# WIFI.net
KiCad netlist of a schematic drawn in Altium Designer
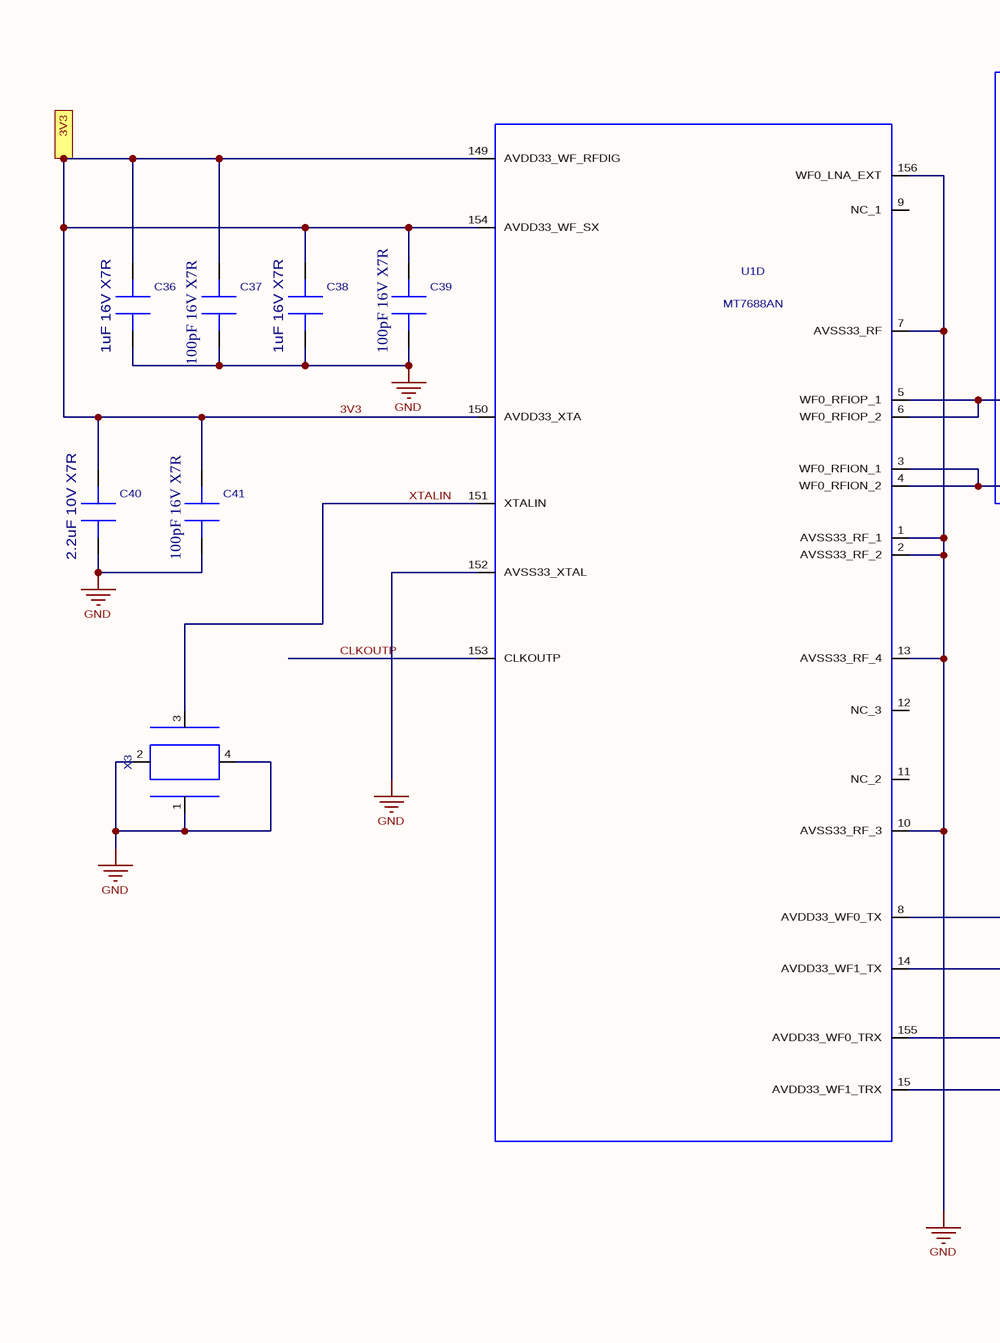
[diagram p0: WIFI.SchDoc, left]
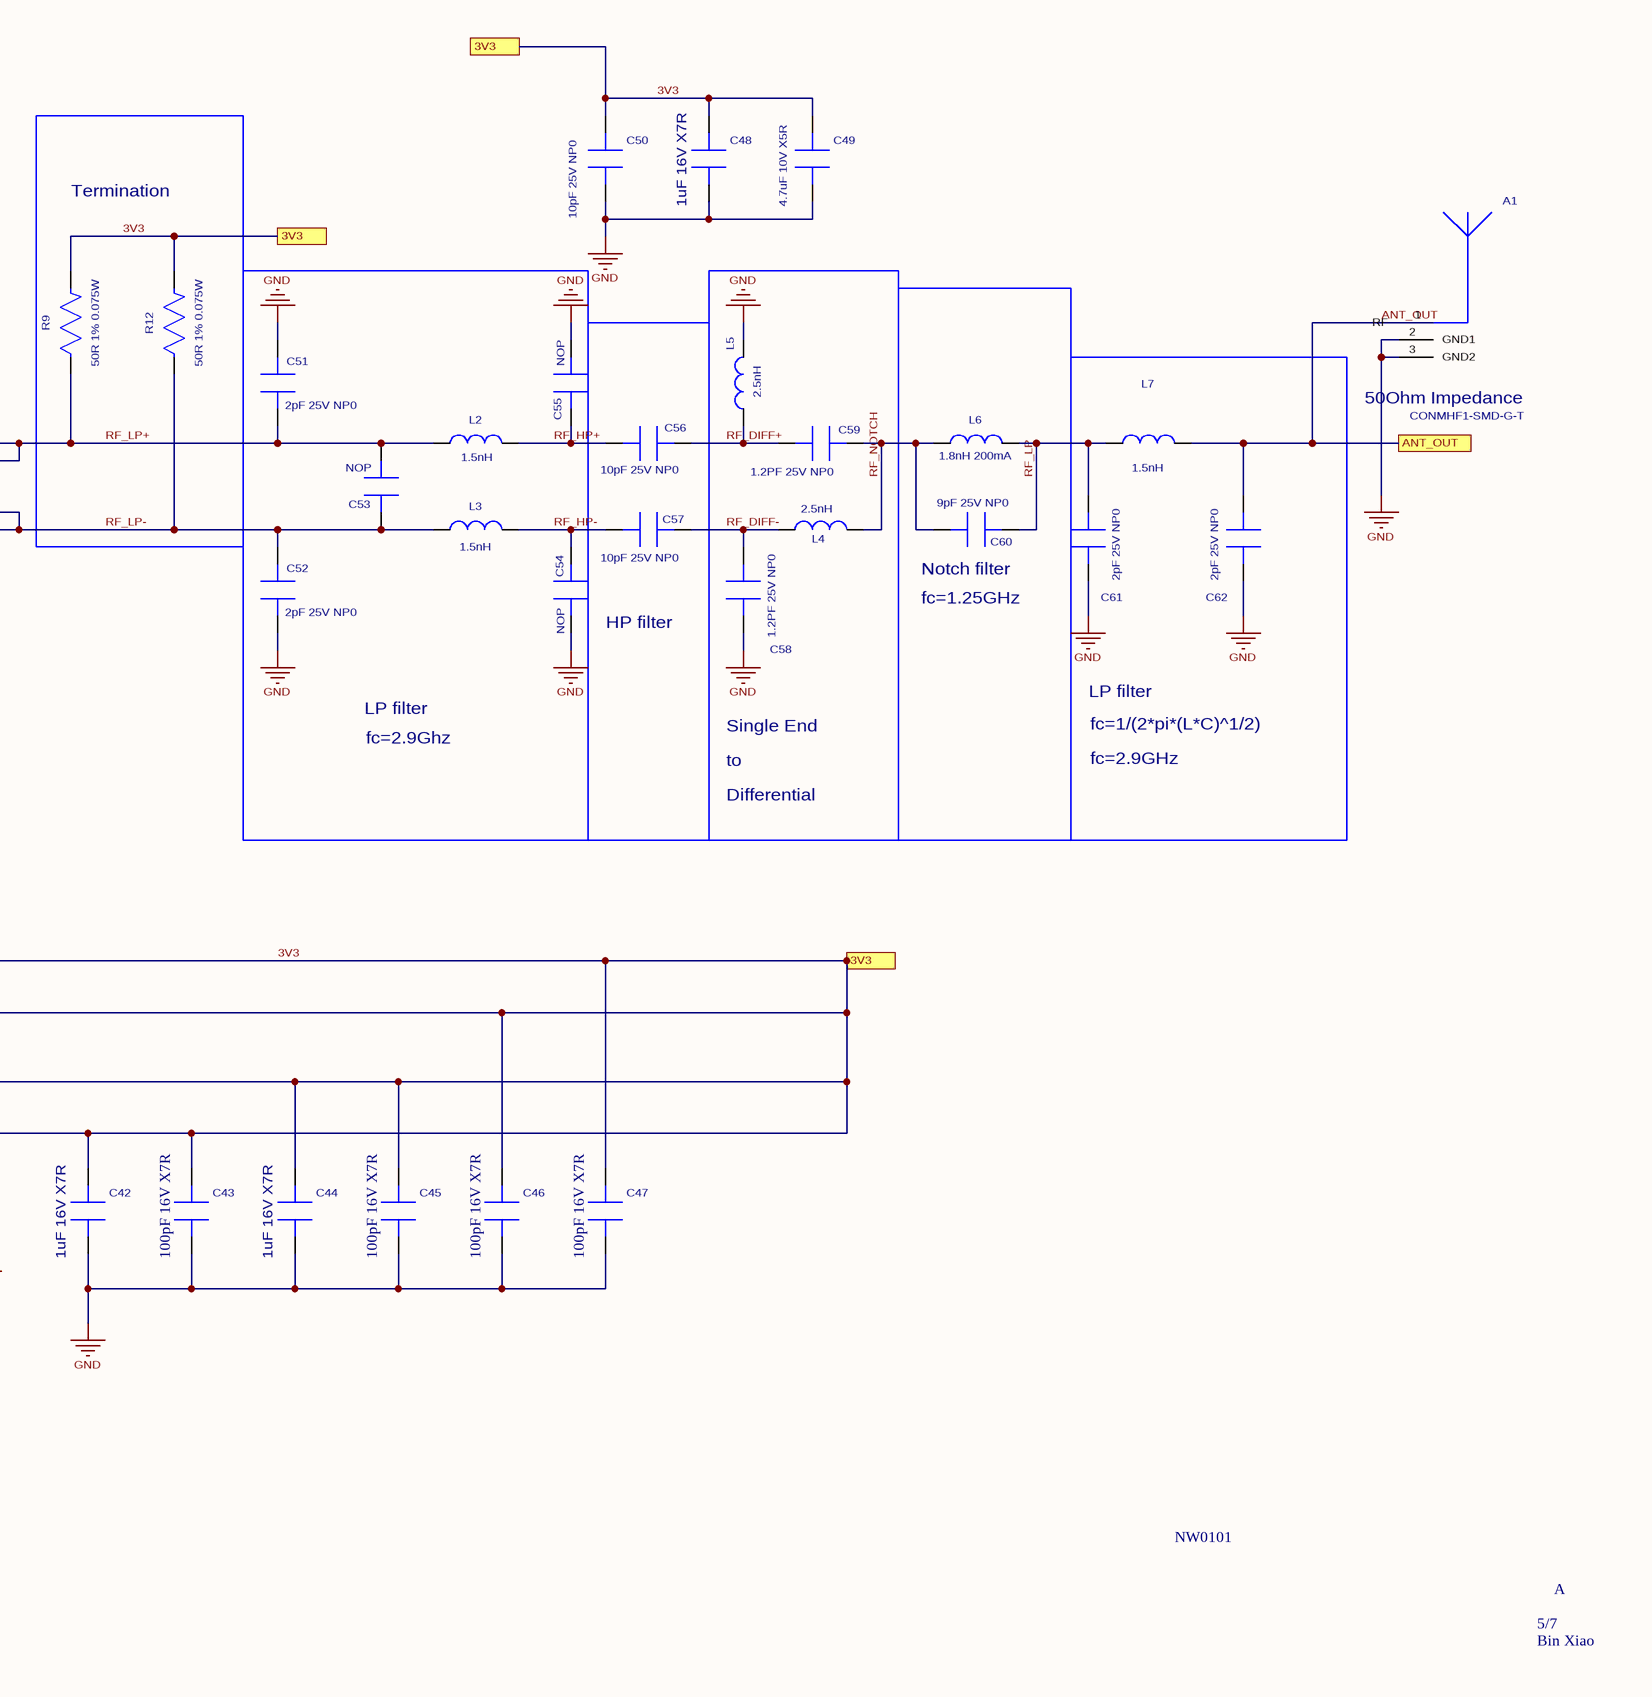
[diagram p1: WIFI.SchDoc, right]

(export (version "E")
  (design (tool "Eeschema 10.0.6"))
  (components
    (comp (ref "A1")
      (value "CONMHF1-SMD-G-T")
      (footprint "CONMHF1-SMD-G-T")
      (description "CONN UMC JACK STR SMD")
      (fields (field (name "MANUFACTURER") "Linx Technologies Inc."))
      (libsource (lib "*") (part "CONMHF1-SMD-G-T"))
    )
    (comp (ref "C36")
      (value "1uF 16V X7R")
      (footprint "C0402")
      (description "CAP CER 1UF 6.3V X7R 0402")
      (fields
        (field (name "PART NUMBER") "GRM155R70J105KA12D")
        (field (name "MANUFACTURER") "Murata Electronics")
      )
      (libsource (lib "NetworkModule") (part "CAP0402-105-6.3V-X7R"))
    )
    (comp (ref "C37")
      (value "100pF 16V X7R")
      (footprint "C0201")
      (description "CAP CER 100PF 16V X7R 0201")
      (fields
        (field (name "PART NUMBER") "0201B101K160CT")
        (field (name "MANUFACTURER") "Walsin Technology Corporation")
      )
      (libsource (lib "NetworkModule") (part "CAP0201-101-16V-X7R"))
    )
    (comp (ref "C38")
      (value "1uF 16V X7R")
      (footprint "C0402")
      (description "CAP CER 1UF 6.3V X7R 0402")
      (fields
        (field (name "PART NUMBER") "GRM155R70J105KA12D")
        (field (name "MANUFACTURER") "Murata Electronics")
      )
      (libsource (lib "NetworkModule") (part "CAP0402-105-6.3V-X7R"))
    )
    (comp (ref "C39")
      (value "100pF 16V X7R")
      (footprint "C0201")
      (description "CAP CER 100PF 16V X7R 0201")
      (fields
        (field (name "PART NUMBER") "0201B101K160CT")
        (field (name "MANUFACTURER") "Walsin Technology Corporation")
      )
      (libsource (lib "NetworkModule") (part "CAP0201-101-16V-X7R"))
    )
    (comp (ref "C40")
      (value "2.2uF 10V X7R")
      (footprint "C0402")
      (description "CAP CER 2.2UF 10V X7R 0402")
      (fields
        (field (name "PART NUMBER") "GRM155Z71A225KE01D")
        (field (name "MANUFACTURER") "Murata Electronics")
      )
      (libsource (lib "NetworkModule") (part "CAP0402-225-6.3V-X7R"))
    )
    (comp (ref "C41")
      (value "100pF 16V X7R")
      (footprint "C0201")
      (description "CAP CER 100PF 16V X7R 0201")
      (fields
        (field (name "PART NUMBER") "0201B101K160CT")
        (field (name "MANUFACTURER") "Walsin Technology Corporation")
      )
      (libsource (lib "NetworkModule") (part "CAP0201-101-16V-X7R"))
    )
    (comp (ref "C42")
      (value "1uF 16V X7R")
      (footprint "C0402")
      (description "CAP CER 1UF 6.3V X7R 0402")
      (fields
        (field (name "PART NUMBER") "GRM155R70J105KA12D")
        (field (name "MANUFACTURER") "Murata Electronics")
      )
      (libsource (lib "NetworkModule") (part "CAP0402-105-6.3V-X7R"))
    )
    (comp (ref "C43")
      (value "100pF 16V X7R")
      (footprint "C0201")
      (description "CAP CER 100PF 16V X7R 0201")
      (fields
        (field (name "PART NUMBER") "0201B101K160CT")
        (field (name "MANUFACTURER") "Walsin Technology Corporation")
      )
      (libsource (lib "NetworkModule") (part "CAP0201-101-16V-X7R"))
    )
    (comp (ref "C44")
      (value "1uF 16V X7R")
      (footprint "C0402")
      (description "CAP CER 1UF 6.3V X7R 0402")
      (fields
        (field (name "PART NUMBER") "GRM155R70J105KA12D")
        (field (name "MANUFACTURER") "Murata Electronics")
      )
      (libsource (lib "NetworkModule") (part "CAP0402-105-6.3V-X7R"))
    )
    (comp (ref "C45")
      (value "100pF 16V X7R")
      (footprint "C0201")
      (description "CAP CER 100PF 16V X7R 0201")
      (fields
        (field (name "PART NUMBER") "0201B101K160CT")
        (field (name "MANUFACTURER") "Walsin Technology Corporation")
      )
      (libsource (lib "NetworkModule") (part "CAP0201-101-16V-X7R"))
    )
    (comp (ref "C46")
      (value "100pF 16V X7R")
      (footprint "C0201")
      (description "CAP CER 100PF 16V X7R 0201")
      (fields
        (field (name "PART NUMBER") "0201B101K160CT")
        (field (name "MANUFACTURER") "Walsin Technology Corporation")
      )
      (libsource (lib "NetworkModule") (part "CAP0201-101-16V-X7R"))
    )
    (comp (ref "C47")
      (value "100pF 16V X7R")
      (footprint "C0201")
      (description "CAP CER 100PF 16V X7R 0201")
      (fields
        (field (name "PART NUMBER") "0201B101K160CT")
        (field (name "MANUFACTURER") "Walsin Technology Corporation")
      )
      (libsource (lib "NetworkModule") (part "CAP0201-101-16V-X7R"))
    )
    (comp (ref "C48")
      (value "1uF 16V X7R")
      (footprint "C0402")
      (description "CAP CER 1UF 6.3V X7R 0402")
      (fields
        (field (name "PART NUMBER") "GRM155R70J105KA12D")
        (field (name "MANUFACTURER") "Murata Electronics")
      )
      (libsource (lib "NetworkModule") (part "CAP0402-105-6.3V-X7R"))
    )
    (comp (ref "C49")
      (value "4.7uF 10V X5R")
      (footprint "C0402")
      (description "CAP CER 4.7UF 10V X5R 0402")
      (fields
        (field (name "PART NUMBER") "CL05A475MP5NRNC")
        (field (name "MANUFACTURER") "Samsung Electro-Mechanics")
      )
      (libsource (lib "NetworkModule") (part "CAP0402-475-10V-X5R"))
    )
    (comp (ref "C50")
      (value "10pF 25V NP0")
      (footprint "C0201")
      (description "CAP CER 10PF 25V C0G/NP0 0201")
      (fields
        (field (name "PART NUMBER") "0201N100J250CT")
        (field (name "MANUFACTURER") "Walsin Technology Corporation")
      )
      (libsource (lib "NetworkModule") (part "CAP0201-100-25V-NP0"))
    )
    (comp (ref "C51")
      (value "2pF 25V NP0")
      (footprint "C0201")
      (description "CAP CER 2PF 25V C0G/NP0 0201")
      (fields
        (field (name "PART NUMBER") "CL03C020BA3GNNC")
        (field (name "MANUFACTURER") "Samsung Electro-Mechanics")
      )
      (libsource (lib "NetworkModule") (part "CAP0201-020-25V-NP0"))
    )
    (comp (ref "C52")
      (value "2pF 25V NP0")
      (footprint "C0201")
      (description "CAP CER 2PF 25V C0G/NP0 0201")
      (fields
        (field (name "PART NUMBER") "CL03C020BA3GNNC")
        (field (name "MANUFACTURER") "Samsung Electro-Mechanics")
      )
      (libsource (lib "NetworkModule") (part "CAP0201-020-25V-NP0"))
    )
    (comp (ref "C53")
      (value "NOP")
      (footprint "C0201_NOP")
      (fields (field (name "Comment") "CAP0201-NOP"))
      (libsource (lib "NetworkModule") (part "CAP0201-NOP"))
    )
    (comp (ref "C54")
      (value "NOP")
      (footprint "C0201_NOP")
      (fields (field (name "Comment") "CAP0201-NOP"))
      (libsource (lib "NetworkModule") (part "CAP0201-NOP"))
    )
    (comp (ref "C55")
      (value "NOP")
      (footprint "C0201_NOP")
      (fields (field (name "Comment") "CAP0201-NOP"))
      (libsource (lib "NetworkModule") (part "CAP0201-NOP"))
    )
    (comp (ref "C56")
      (value "10pF 25V NP0")
      (footprint "C0201")
      (description "CAP CER 10PF 25V C0G/NP0 0201")
      (fields
        (field (name "PART NUMBER") "0201N100J250CT")
        (field (name "MANUFACTURER") "Walsin Technology Corporation")
      )
      (libsource (lib "NetworkModule") (part "CAP0201-100-25V-NP0"))
    )
    (comp (ref "C57")
      (value "10pF 25V NP0")
      (footprint "C0201")
      (description "CAP CER 10PF 25V C0G/NP0 0201")
      (fields
        (field (name "PART NUMBER") "0201N100J250CT")
        (field (name "MANUFACTURER") "Walsin Technology Corporation")
      )
      (libsource (lib "NetworkModule") (part "CAP0201-100-25V-NP0"))
    )
    (comp (ref "C58")
      (value "1.2PF 25V NP0")
      (footprint "C0201")
      (description "CAP CER 1.2PF 25V C0G/NP0 0201")
      (fields
        (field (name "PART NUMBER") "GRM0335C1E1R2WA01D")
        (field (name "MANUFACTURER") "Murata Electronics")
      )
      (libsource (lib "NetworkModule") (part "CAP0201-1R2-25V-NP0"))
    )
    (comp (ref "C59")
      (value "1.2PF 25V NP0")
      (footprint "C0201")
      (description "CAP CER 1.2PF 25V C0G/NP0 0201")
      (fields
        (field (name "PART NUMBER") "GRM0335C1E1R2WA01D")
        (field (name "MANUFACTURER") "Murata Electronics")
      )
      (libsource (lib "NetworkModule") (part "CAP0201-1R2-25V-NP0"))
    )
    (comp (ref "C60")
      (value "9pF 25V NP0")
      (footprint "C0201")
      (description "CAP CER 9PF 25V C0G 0201")
      (fields
        (field (name "PART NUMBER") "CGA1A2C0G1E090D030BA")
        (field (name "MANUFACTURER") "TDK Corporation")
      )
      (libsource (lib "NetworkModule") (part "CAP0201-090-100V-NP0"))
    )
    (comp (ref "C61")
      (value "2pF 25V NP0")
      (footprint "C0201")
      (description "CAP CER 2PF 25V C0G/NP0 0201")
      (fields
        (field (name "PART NUMBER") "CL03C020BA3GNNC")
        (field (name "MANUFACTURER") "Samsung Electro-Mechanics")
      )
      (libsource (lib "NetworkModule") (part "CAP0201-020-25V-NP0"))
    )
    (comp (ref "C62")
      (value "2pF 25V NP0")
      (footprint "C0201")
      (description "CAP CER 2PF 25V C0G/NP0 0201")
      (fields
        (field (name "PART NUMBER") "CL03C020BA3GNNC")
        (field (name "MANUFACTURER") "Samsung Electro-Mechanics")
      )
      (libsource (lib "NetworkModule") (part "CAP0201-020-25V-NP0"))
    )
    (comp (ref "L2")
      (value "1.5nH")
      (footprint "L0201")
      (description "INDUCTOR FIXED 1.5NH 0201")
      (fields
        (field (name "PART NUMBER") "WLCM0603TGB1N5TB")
        (field (name "MANUFACTURER") "Walsin Technology Corporation")
      )
      (libsource (lib "NetworkModule") (part "IND0201_1.5N_600MA"))
    )
    (comp (ref "L3")
      (value "1.5nH")
      (footprint "L0201")
      (description "INDUCTOR FIXED 1.5NH 0201")
      (fields
        (field (name "PART NUMBER") "WLCM0603TGB1N5TB")
        (field (name "MANUFACTURER") "Walsin Technology Corporation")
      )
      (libsource (lib "NetworkModule") (part "IND0201_1.5N_600MA"))
    )
    (comp (ref "L4")
      (value "2.5nH")
      (footprint "L0201")
      (description "FIXED IND 2.5NH 500MA 200MOHM SM")
      (fields
        (field (name "PART NUMBER") "LQP03TN2N5B02D")
        (field (name "MANUFACTURER") "Murata Electronics")
      )
      (libsource (lib "NetworkModule") (part "IND0201_2.5N_500MA"))
    )
    (comp (ref "L5")
      (value "2.5nH")
      (footprint "L0201")
      (description "FIXED IND 2.5NH 500MA 200MOHM SM")
      (fields
        (field (name "PART NUMBER") "LQP03TN2N5B02D")
        (field (name "MANUFACTURER") "Murata Electronics")
      )
      (libsource (lib "NetworkModule") (part "IND0201_2.5N_500MA"))
    )
    (comp (ref "L6")
      (value "1.8nH 200mA")
      (footprint "L0201")
      (description "FIXED IND 1.8NH 200MA 550MOHM SM")
      (fields
        (field (name "PART NUMBER") "1-2176075-8")
        (field (name "MANUFACTURER") "TE Connectivity Passive Product")
      )
      (libsource (lib "NetworkModule") (part "IND0201_1.8N_200MA"))
    )
    (comp (ref "L7")
      (value "1.5nH")
      (footprint "L0201")
      (description "INDUCTOR FIXED 1.5NH 0201")
      (fields
        (field (name "PART NUMBER") "WLCM0603TGB1N5TB")
        (field (name "MANUFACTURER") "Walsin Technology Corporation")
      )
      (libsource (lib "NetworkModule") (part "IND0201_1.5N_600MA"))
    )
    (comp (ref "R9")
      (value "50R 1% 0.075W")
      (footprint "R0201")
      (description "RES 50 OHM 0.1% 0.075W 0201")
      (fields (field (name "MANUFACTURER") "Vishay Dale") (field (name "PART NUMBER") "TNPW020150R0BEED"))
      (libsource (lib "NetworkModule") (part "RES0201-50R0"))
    )
    (comp (ref "R12")
      (value "50R 1% 0.075W")
      (footprint "R0201")
      (description "RES 50 OHM 0.1% 0.075W 0201")
      (fields (field (name "MANUFACTURER") "Vishay Dale") (field (name "PART NUMBER") "TNPW020150R0BEED"))
      (libsource (lib "NetworkModule") (part "RES0201-50R0"))
    )
    (comp (ref "U1")
      (value "MT7688AN")
      (footprint "DR-QFN-128")
      (description "580Mhz 32bits Networking Processor")
      (fields (field (name "MANUFACTURER") "MediaTek Inc"))
      (libsource (lib "*") (part "MT7688AN"))
    )
    (comp (ref "X3")
      (value "R2520-40.000-12-F-1010-TR-NS1")
      (footprint "R2520-40.000-12-F-1010-TR-NS1")
      (description "CRYSTAL 40.0000MHZ 12PF SMD")
      (fields (field (name "MANUFACTURER") "Raltron Electronics"))
      (libsource (lib "*") (part "R2520-40.000-12-F-1010-TR-NS1"))
    )
  )
  (nets
    (net (code "1") (name "/3V3") (class "Default")
      (node (ref "C36") (pin "1") (pinfunction "1_1") (pintype "passive"))
      (node (ref "C37") (pin "1") (pinfunction "1_1") (pintype "passive"))
      (node (ref "C38") (pin "1") (pinfunction "1_1") (pintype "passive"))
      (node (ref "C39") (pin "1") (pinfunction "1_1") (pintype "passive"))
      (node (ref "C40") (pin "1") (pinfunction "1_1") (pintype "passive"))
      (node (ref "C41") (pin "1") (pinfunction "1_1") (pintype "passive"))
      (node (ref "C42") (pin "1") (pinfunction "1_1") (pintype "passive"))
      (node (ref "C43") (pin "1") (pinfunction "1_1") (pintype "passive"))
      (node (ref "C44") (pin "1") (pinfunction "1_1") (pintype "passive"))
      (node (ref "C45") (pin "1") (pinfunction "1_1") (pintype "passive"))
      (node (ref "C46") (pin "1") (pinfunction "1_1") (pintype "passive"))
      (node (ref "C47") (pin "1") (pinfunction "1_1") (pintype "passive"))
      (node (ref "C48") (pin "1") (pinfunction "1_1") (pintype "passive"))
      (node (ref "C49") (pin "1") (pinfunction "1_1") (pintype "passive"))
      (node (ref "C50") (pin "1") (pinfunction "1_1") (pintype "passive"))
      (node (ref "R12") (pin "2") (pinfunction "2_2") (pintype "passive"))
      (node (ref "R9") (pin "2") (pinfunction "2_2") (pintype "passive"))
      (node (ref "U1") (pin "14") (pinfunction "AVDD33_WF1_TX_14") (pintype "passive"))
      (node (ref "U1") (pin "149") (pinfunction "AVDD33_WF_RFDIG_149") (pintype "passive"))
      (node (ref "U1") (pin "15") (pinfunction "AVDD33_WF1_TRX_15") (pintype "passive"))
      (node (ref "U1") (pin "150") (pinfunction "AVDD33_XTA_150") (pintype "passive"))
      (node (ref "U1") (pin "154") (pinfunction "AVDD33_WF_SX_154") (pintype "passive"))
      (node (ref "U1") (pin "155") (pinfunction "AVDD33_WF0_TRX_155") (pintype "passive"))
      (node (ref "U1") (pin "8") (pinfunction "AVDD33_WF0_TX_8") (pintype "passive"))
    )
    (net (code "2") (name "/ANT_OUT") (class "Default")
      (node (ref "A1") (pin "1") (pinfunction "RF_1") (pintype "passive"))
      (node (ref "C62") (pin "1") (pinfunction "1_1") (pintype "passive"))
      (node (ref "L7") (pin "2") (pinfunction "2_2") (pintype "passive"))
    )
    (net (code "3") (name "/CLKOUTP") (class "Default")
      (node (ref "U1") (pin "153") (pinfunction "CLKOUTP_153") (pintype "passive"))
    )
    (net (code "4") (name "/RF_DIFF+") (class "Default")
      (node (ref "C56") (pin "1") (pinfunction "1_1") (pintype "passive"))
      (node (ref "C59") (pin "2") (pinfunction "2_2") (pintype "passive"))
      (node (ref "L5") (pin "1") (pinfunction "1_1") (pintype "passive"))
    )
    (net (code "5") (name "/RF_DIFF-") (class "Default")
      (node (ref "C57") (pin "1") (pinfunction "1_1") (pintype "passive"))
      (node (ref "C58") (pin "1") (pinfunction "1_1") (pintype "passive"))
      (node (ref "L4") (pin "1") (pinfunction "1_1") (pintype "passive"))
    )
    (net (code "6") (name "/RF_HP+") (class "Default")
      (node (ref "C55") (pin "1") (pinfunction "1_1") (pintype "passive"))
      (node (ref "C56") (pin "2") (pinfunction "2_2") (pintype "passive"))
      (node (ref "L2") (pin "2") (pinfunction "2_2") (pintype "passive"))
    )
    (net (code "7") (name "/RF_HP-") (class "Default")
      (node (ref "C54") (pin "1") (pinfunction "1_1") (pintype "passive"))
      (node (ref "C57") (pin "2") (pinfunction "2_2") (pintype "passive"))
      (node (ref "L3") (pin "2") (pinfunction "2_2") (pintype "passive"))
    )
    (net (code "8") (name "/RF_LP") (class "Default")
      (node (ref "C60") (pin "1") (pinfunction "1_1") (pintype "passive"))
      (node (ref "C61") (pin "1") (pinfunction "1_1") (pintype "passive"))
      (node (ref "L6") (pin "2") (pinfunction "2_2") (pintype "passive"))
      (node (ref "L7") (pin "1") (pinfunction "1_1") (pintype "passive"))
    )
    (net (code "9") (name "/RF_LP+") (class "Default")
      (node (ref "C51") (pin "2") (pinfunction "2_2") (pintype "passive"))
      (node (ref "C53") (pin "1") (pinfunction "1_1") (pintype "passive"))
      (node (ref "L2") (pin "1") (pinfunction "1_1") (pintype "passive"))
      (node (ref "R9") (pin "1") (pinfunction "1_1") (pintype "passive"))
      (node (ref "U1") (pin "5") (pinfunction "WF0_RFIOP_1_5") (pintype "passive"))
      (node (ref "U1") (pin "6") (pinfunction "WF0_RFIOP_2_6") (pintype "passive"))
    )
    (net (code "10") (name "/RF_LP-") (class "Default")
      (node (ref "C52") (pin "1") (pinfunction "1_1") (pintype "passive"))
      (node (ref "C53") (pin "2") (pinfunction "2_2") (pintype "passive"))
      (node (ref "L3") (pin "1") (pinfunction "1_1") (pintype "passive"))
      (node (ref "R12") (pin "1") (pinfunction "1_1") (pintype "passive"))
      (node (ref "U1") (pin "3") (pinfunction "WF0_RFION_1_3") (pintype "passive"))
      (node (ref "U1") (pin "4") (pinfunction "WF0_RFION_2_4") (pintype "passive"))
    )
    (net (code "11") (name "/RF_NOTCH") (class "Default")
      (node (ref "C59") (pin "1") (pinfunction "1_1") (pintype "passive"))
      (node (ref "C60") (pin "2") (pinfunction "2_2") (pintype "passive"))
      (node (ref "L4") (pin "2") (pinfunction "2_2") (pintype "passive"))
      (node (ref "L6") (pin "1") (pinfunction "1_1") (pintype "passive"))
    )
    (net (code "12") (name "/XTALIN") (class "Default")
      (node (ref "U1") (pin "151") (pinfunction "XTALIN_151") (pintype "passive"))
      (node (ref "X3") (pin "3") (pinfunction "3_3") (pintype "passive"))
    )
    (net (code "13") (name "GND") (class "Default")
      (node (ref "A1") (pin "2") (pinfunction "GND1_2") (pintype "passive"))
      (node (ref "A1") (pin "3") (pinfunction "GND2_3") (pintype "passive"))
      (node (ref "C36") (pin "2") (pinfunction "2_2") (pintype "passive"))
      (node (ref "C37") (pin "2") (pinfunction "2_2") (pintype "passive"))
      (node (ref "C38") (pin "2") (pinfunction "2_2") (pintype "passive"))
      (node (ref "C39") (pin "2") (pinfunction "2_2") (pintype "passive"))
      (node (ref "C40") (pin "2") (pinfunction "2_2") (pintype "passive"))
      (node (ref "C41") (pin "2") (pinfunction "2_2") (pintype "passive"))
      (node (ref "C42") (pin "2") (pinfunction "2_2") (pintype "passive"))
      (node (ref "C43") (pin "2") (pinfunction "2_2") (pintype "passive"))
      (node (ref "C44") (pin "2") (pinfunction "2_2") (pintype "passive"))
      (node (ref "C45") (pin "2") (pinfunction "2_2") (pintype "passive"))
      (node (ref "C46") (pin "2") (pinfunction "2_2") (pintype "passive"))
      (node (ref "C47") (pin "2") (pinfunction "2_2") (pintype "passive"))
      (node (ref "C48") (pin "2") (pinfunction "2_2") (pintype "passive"))
      (node (ref "C49") (pin "2") (pinfunction "2_2") (pintype "passive"))
      (node (ref "C50") (pin "2") (pinfunction "2_2") (pintype "passive"))
      (node (ref "C51") (pin "1") (pinfunction "1_1") (pintype "passive"))
      (node (ref "C52") (pin "2") (pinfunction "2_2") (pintype "passive"))
      (node (ref "C54") (pin "2") (pinfunction "2_2") (pintype "passive"))
      (node (ref "C55") (pin "2") (pinfunction "2_2") (pintype "passive"))
      (node (ref "C58") (pin "2") (pinfunction "2_2") (pintype "passive"))
      (node (ref "C61") (pin "2") (pinfunction "2_2") (pintype "passive"))
      (node (ref "C62") (pin "2") (pinfunction "2_2") (pintype "passive"))
      (node (ref "L5") (pin "2") (pinfunction "2_2") (pintype "passive"))
      (node (ref "U1") (pin "1") (pinfunction "AVSS33_RF_1_1") (pintype "passive"))
      (node (ref "U1") (pin "10") (pinfunction "AVSS33_RF_3_10") (pintype "passive"))
      (node (ref "U1") (pin "13") (pinfunction "AVSS33_RF_4_13") (pintype "passive"))
      (node (ref "U1") (pin "152") (pinfunction "AVSS33_XTAL_152") (pintype "passive"))
      (node (ref "U1") (pin "156") (pinfunction "WF0_LNA_EXT_156") (pintype "passive"))
      (node (ref "U1") (pin "2") (pinfunction "AVSS33_RF_2_2") (pintype "passive"))
      (node (ref "U1") (pin "7") (pinfunction "AVSS33_RF_7") (pintype "passive"))
      (node (ref "X3") (pin "1") (pinfunction "1_1") (pintype "passive"))
      (node (ref "X3") (pin "2") (pinfunction "GND1_2") (pintype "passive"))
      (node (ref "X3") (pin "4") (pinfunction "GND2_4") (pintype "passive"))
    )
    (net (code "14") (name "unconnected-(U1D-NC_1-Pad9)") (class "Default")
      (node (ref "U1") (pin "9") (pinfunction "NC_1_9") (pintype "passive"))
    )
    (net (code "15") (name "unconnected-(U1D-NC_2-Pad11)") (class "Default")
      (node (ref "U1") (pin "11") (pinfunction "NC_2_11") (pintype "passive"))
    )
    (net (code "16") (name "unconnected-(U1D-NC_3-Pad12)") (class "Default")
      (node (ref "U1") (pin "12") (pinfunction "NC_3_12") (pintype "passive"))
    )
  )
)
